# PWR_MGMT.net
KiCad netlist of a schematic drawn in Altium Designer
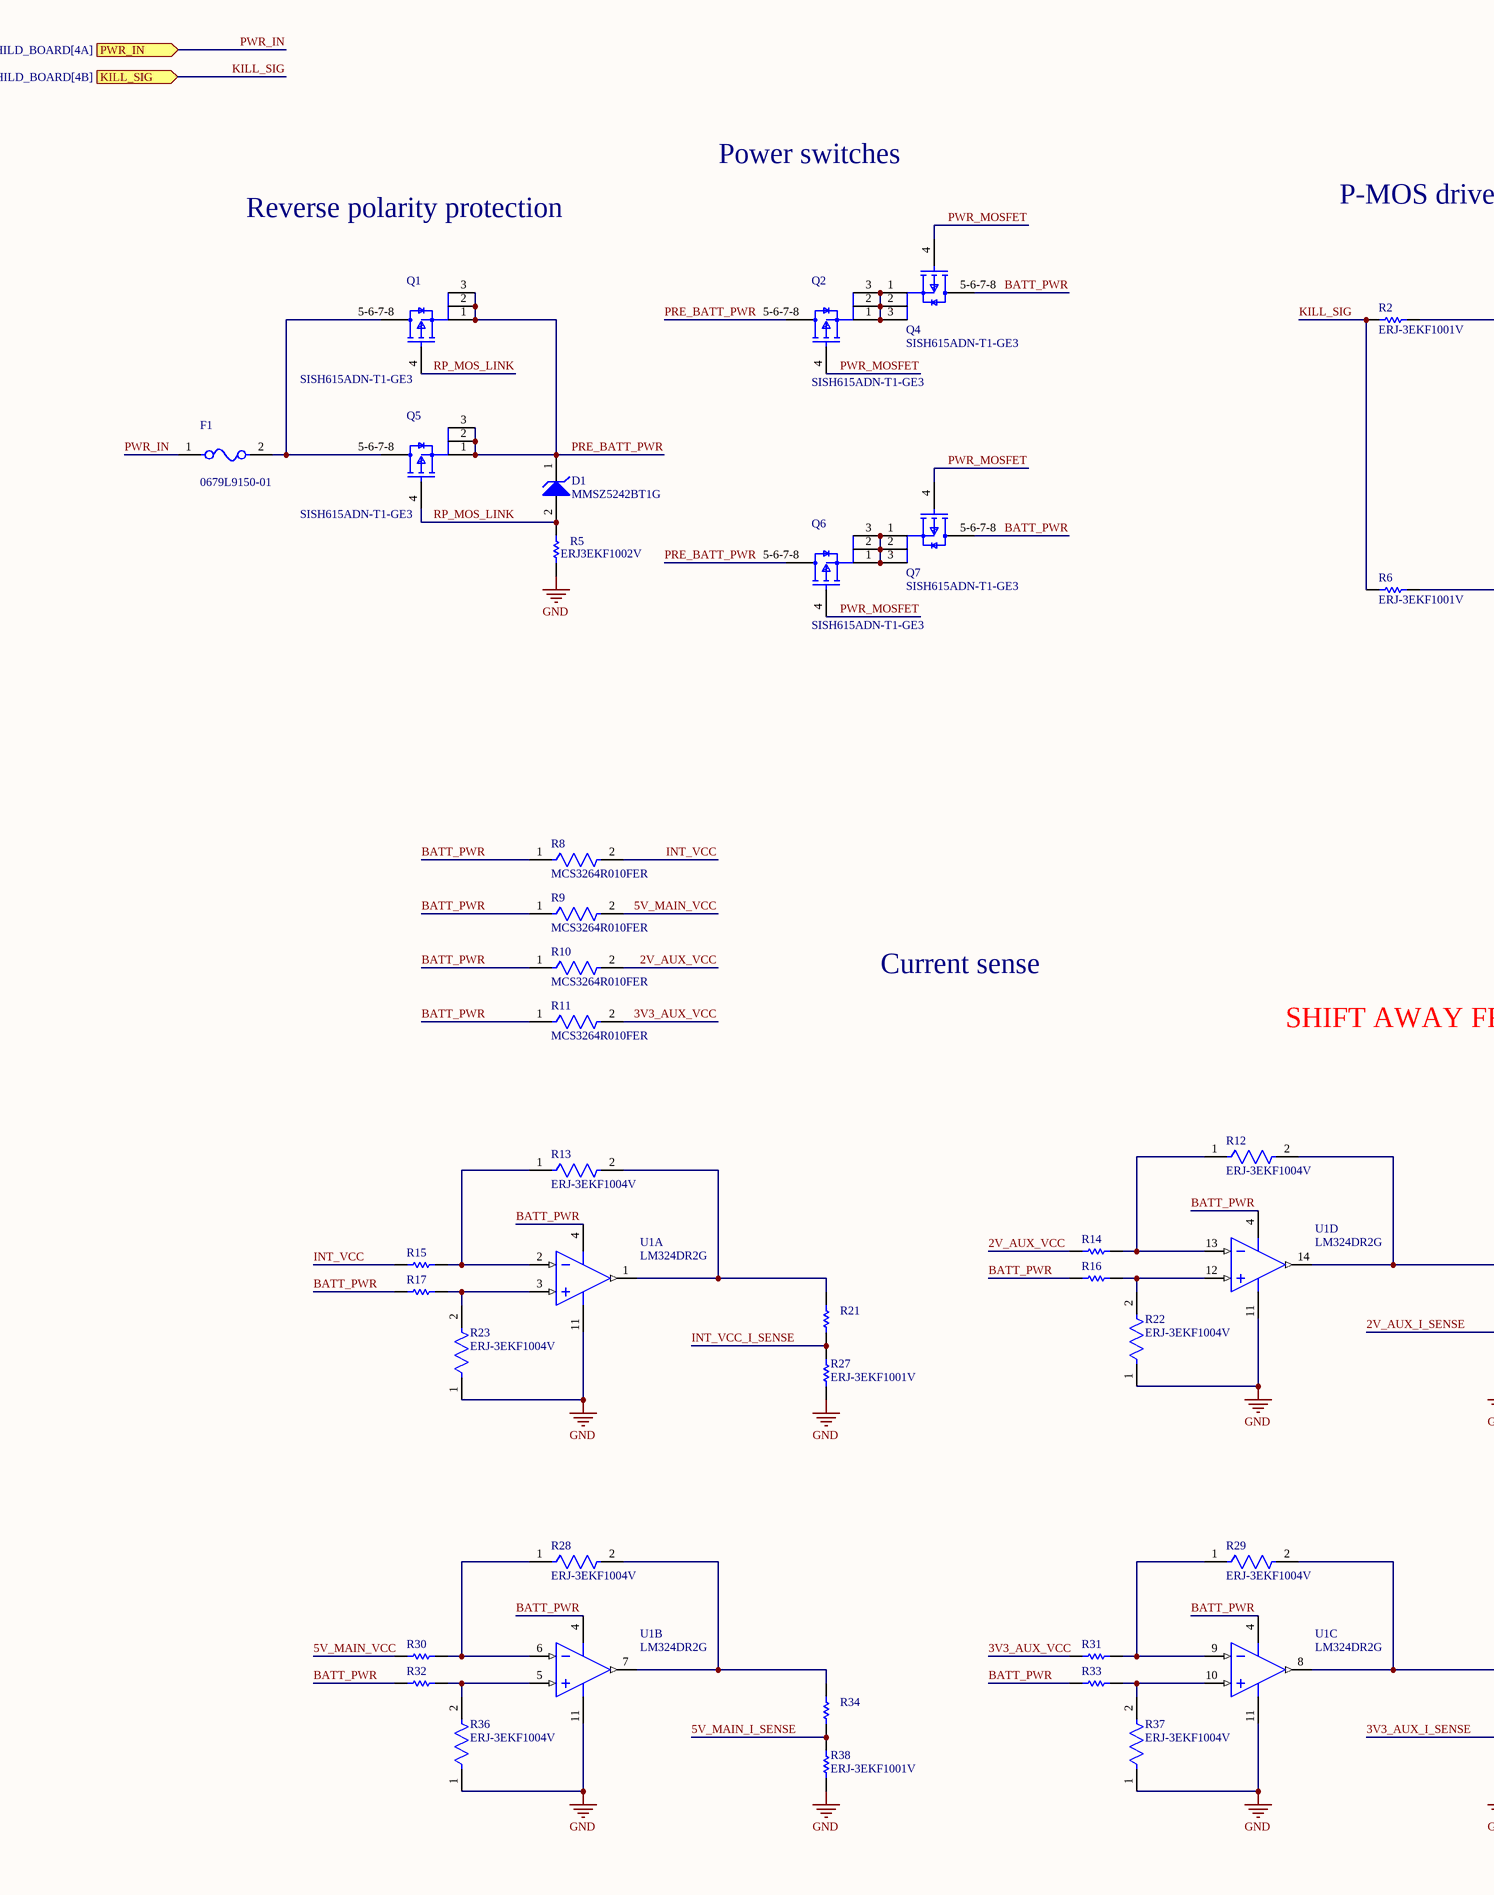
[diagram p0: PWR_MGMT.SchDoc, left]
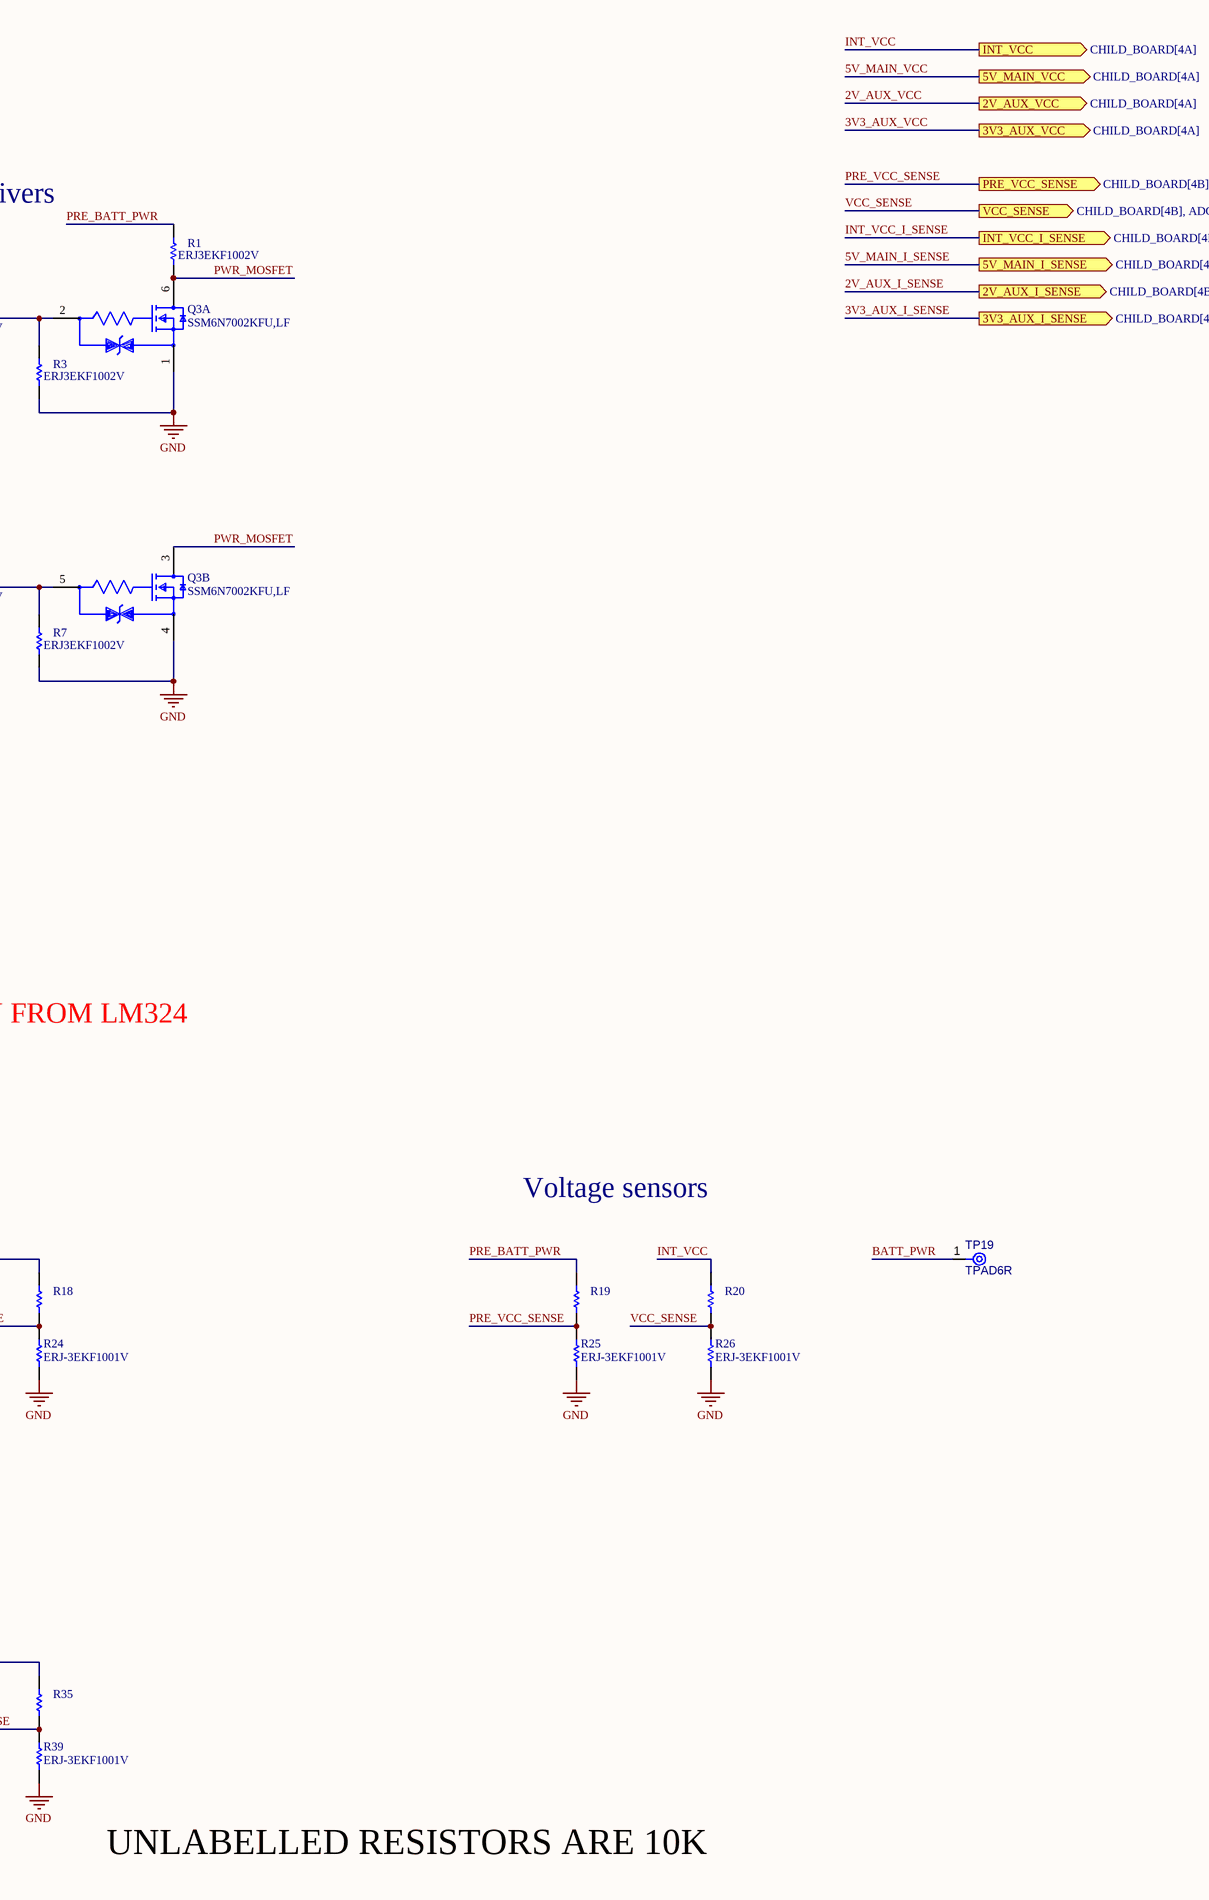
[diagram p1: PWR_MGMT.SchDoc, right]

(export (version "E")
  (design (tool "Eeschema 10.0.6"))
  (components
    (comp (ref "D1")
      (value "MMSZ5242BT1G")
      (footprint "ONSC-SOD-123-2-425-04_V")
      (description "Zener Voltage Regulator, 500 mW, 2-Pin SOD-123, Pb-Free, Tape and Reel")
      (fields (field (name "MANUFACTURER") "On Semiconductor"))
      (libsource (lib "Altium Content Vault") (part "ONSC-K1A2-2"))
    )
    (comp (ref "F1")
      (value "0679L9150-01")
      (footprint "FP-0679L-MFG")
      (description "FUSE BRD MNT 15A 125VAC/VDC")
      (fields
        (field (name "OCTOPART") "https://octopart.com/0679l9150-01-bel+fuse-70850665")
        (field (name "MANUFACTURER") "Bel Fuse")
      )
      (libsource (lib "Altium Content Vault") (part "5bcf9b9f640e542cf0359d10258e979"))
    )
    (comp (ref "Q1")
      (value "SISH615ADN-T1-GE3")
      (footprint "SISH615ADN-T1-GE3-Footprint-1")
      (description "Trans MOSFET P-CH 20V 22.1A 8-Pin PowerPAK 1212 EP T/R")
      (libsource (lib "uORocketry Hardware") (part "SISH615ADN-T1-GE3-Symbol-1"))
    )
    (comp (ref "Q2")
      (value "SISH615ADN-T1-GE3")
      (footprint "SISH615ADN-T1-GE3-Footprint-1")
      (description "Trans MOSFET P-CH 20V 22.1A 8-Pin PowerPAK 1212 EP T/R")
      (libsource (lib "uORocketry Hardware") (part "SISH615ADN-T1-GE3-Symbol-1"))
    )
    (comp (ref "Q3")
      (value "SSM6N7002KFU,LF")
      (footprint "FP-SSOP6-P-0_65A-MFG")
      (description "MOSFET 2N-CH 60V 0.3A")
      (libsource (lib "Altium Content Vault") (part "088aa6ac103fdeebe0d1c52ece6b7b9"))
    )
    (comp (ref "Q4")
      (value "SISH615ADN-T1-GE3")
      (footprint "SISH615ADN-T1-GE3-Footprint-1")
      (description "Trans MOSFET P-CH 20V 22.1A 8-Pin PowerPAK 1212 EP T/R")
      (libsource (lib "uORocketry Hardware") (part "SISH615ADN-T1-GE3-Symbol-1"))
    )
    (comp (ref "Q5")
      (value "SISH615ADN-T1-GE3")
      (footprint "SISH615ADN-T1-GE3-Footprint-1")
      (description "Trans MOSFET P-CH 20V 22.1A 8-Pin PowerPAK 1212 EP T/R")
      (libsource (lib "uORocketry Hardware") (part "SISH615ADN-T1-GE3-Symbol-1"))
    )
    (comp (ref "Q6")
      (value "SISH615ADN-T1-GE3")
      (footprint "SISH615ADN-T1-GE3-Footprint-1")
      (description "Trans MOSFET P-CH 20V 22.1A 8-Pin PowerPAK 1212 EP T/R")
      (libsource (lib "uORocketry Hardware") (part "SISH615ADN-T1-GE3-Symbol-1"))
    )
    (comp (ref "Q7")
      (value "SISH615ADN-T1-GE3")
      (footprint "SISH615ADN-T1-GE3-Footprint-1")
      (description "Trans MOSFET P-CH 20V 22.1A 8-Pin PowerPAK 1212 EP T/R")
      (libsource (lib "uORocketry Hardware") (part "SISH615ADN-T1-GE3-Symbol-1"))
    )
    (comp (ref "R1")
      (value "ERJ3EKF1002V")
      (footprint "RESC1609X55X30LL15T15")
      (description "Chip Resistor, 10 KOhm, +/- 1%, 0.1 W, -55 to 155 degC, 0603 (1608 Metric), RoHS, Tape and Reel")
      (fields (field (name "TOLERANCE") "1%") (field (name "MANUFACTURER") "Panasonic"))
      (libsource (lib "Altium Content Vault") (part "RES-2"))
    )
    (comp (ref "R2")
      (value "ERJ-3EKF1001V")
      (footprint "RESC1608X55X30LL15T15")
      (fields (field (name "MANUFACTURER") "Panasonic"))
      (libsource (lib "Altium Content Vault") (part "RES"))
    )
    (comp (ref "R3")
      (value "ERJ3EKF1002V")
      (footprint "RESC1609X55X30LL15T15")
      (description "Chip Resistor, 10 KOhm, +/- 1%, 0.1 W, -55 to 155 degC, 0603 (1608 Metric), RoHS, Tape and Reel")
      (fields (field (name "TOLERANCE") "1%") (field (name "MANUFACTURER") "Panasonic"))
      (libsource (lib "Altium Content Vault") (part "RES-2"))
    )
    (comp (ref "R5")
      (value "ERJ3EKF1002V")
      (footprint "RESC1609X55X30LL15T15")
      (description "Chip Resistor, 10 KOhm, +/- 1%, 0.1 W, -55 to 155 degC, 0603 (1608 Metric), RoHS, Tape and Reel")
      (fields (field (name "TOLERANCE") "1%") (field (name "MANUFACTURER") "Panasonic"))
      (libsource (lib "Altium Content Vault") (part "RES-2"))
    )
    (comp (ref "R6")
      (value "ERJ-3EKF1001V")
      (footprint "RESC1608X55X30LL15T15")
      (fields (field (name "MANUFACTURER") "Panasonic"))
      (libsource (lib "Altium Content Vault") (part "RES"))
    )
    (comp (ref "R7")
      (value "ERJ3EKF1002V")
      (footprint "RESC1609X55X30LL15T15")
      (description "Chip Resistor, 10 KOhm, +/- 1%, 0.1 W, -55 to 155 degC, 0603 (1608 Metric), RoHS, Tape and Reel")
      (fields (field (name "TOLERANCE") "1%") (field (name "MANUFACTURER") "Panasonic"))
      (libsource (lib "Altium Content Vault") (part "RES-2"))
    )
    (comp (ref "R8")
      (value "MCS3264R010FER")
      (footprint "FP-MCS3264-MFG")
      (description "RES SMD 10 MOHM 1% 2W 3264")
      (fields (field (name "TOLERANCE") "1%"))
      (libsource (lib "Altium Content Vault") (part "1029c3af85768c4190bb7ad29bc67b5"))
    )
    (comp (ref "R9")
      (value "MCS3264R010FER")
      (footprint "FP-MCS3264-MFG")
      (description "RES SMD 10 MOHM 1% 2W 3264")
      (fields (field (name "TOLERANCE") "1%"))
      (libsource (lib "Altium Content Vault") (part "1029c3af85768c4190bb7ad29bc67b5"))
    )
    (comp (ref "R10")
      (value "MCS3264R010FER")
      (footprint "FP-MCS3264-MFG")
      (description "RES SMD 10 MOHM 1% 2W 3264")
      (fields (field (name "TOLERANCE") "1%"))
      (libsource (lib "Altium Content Vault") (part "1029c3af85768c4190bb7ad29bc67b5"))
    )
    (comp (ref "R11")
      (value "MCS3264R010FER")
      (footprint "FP-MCS3264-MFG")
      (description "RES SMD 10 MOHM 1% 2W 3264")
      (fields (field (name "TOLERANCE") "1%"))
      (libsource (lib "Altium Content Vault") (part "1029c3af85768c4190bb7ad29bc67b5"))
    )
    (comp (ref "R12")
      (value "ERJ-3EKF1004V")
      (footprint "FP-ERJ3EK-IPC_C")
      (description "RES SMD 1M OHM 1% 1/10W 0603")
      (fields (field (name "TOLERANCE") "1%"))
      (libsource (lib "Altium Content Vault") (part "1029c3af85768c4190bb7ad29bc67b5"))
    )
    (comp (ref "R13")
      (value "ERJ-3EKF1004V")
      (footprint "FP-ERJ3EK-IPC_C")
      (description "RES SMD 1M OHM 1% 1/10W 0603")
      (fields (field (name "TOLERANCE") "1%"))
      (libsource (lib "Altium Content Vault") (part "1029c3af85768c4190bb7ad29bc67b5"))
    )
    (comp (ref "R14")
      (value "ERJ3EKF1002V")
      (footprint "RESC1609X55X30LL15T15")
      (description "Chip Resistor, 10 KOhm, +/- 1%, 0.1 W, -55 to 155 degC, 0603 (1608 Metric), RoHS, Tape and Reel")
      (fields (field (name "TOLERANCE") "1%") (field (name "MANUFACTURER") "Panasonic"))
      (libsource (lib "Altium Content Vault") (part "RES-2"))
    )
    (comp (ref "R15")
      (value "ERJ3EKF1002V")
      (footprint "RESC1609X55X30LL15T15")
      (description "Chip Resistor, 10 KOhm, +/- 1%, 0.1 W, -55 to 155 degC, 0603 (1608 Metric), RoHS, Tape and Reel")
      (fields (field (name "TOLERANCE") "1%") (field (name "MANUFACTURER") "Panasonic"))
      (libsource (lib "Altium Content Vault") (part "RES-2"))
    )
    (comp (ref "R16")
      (value "ERJ3EKF1002V")
      (footprint "RESC1609X55X30LL15T15")
      (description "Chip Resistor, 10 KOhm, +/- 1%, 0.1 W, -55 to 155 degC, 0603 (1608 Metric), RoHS, Tape and Reel")
      (fields (field (name "TOLERANCE") "1%") (field (name "MANUFACTURER") "Panasonic"))
      (libsource (lib "Altium Content Vault") (part "RES-2"))
    )
    (comp (ref "R17")
      (value "ERJ3EKF1002V")
      (footprint "RESC1609X55X30LL15T15")
      (description "Chip Resistor, 10 KOhm, +/- 1%, 0.1 W, -55 to 155 degC, 0603 (1608 Metric), RoHS, Tape and Reel")
      (fields (field (name "TOLERANCE") "1%") (field (name "MANUFACTURER") "Panasonic"))
      (libsource (lib "Altium Content Vault") (part "RES-2"))
    )
    (comp (ref "R18")
      (value "ERJ3EKF1002V")
      (footprint "RESC1609X55X30LL15T15")
      (description "Chip Resistor, 10 KOhm, +/- 1%, 0.1 W, -55 to 155 degC, 0603 (1608 Metric), RoHS, Tape and Reel")
      (fields (field (name "TOLERANCE") "1%") (field (name "MANUFACTURER") "Panasonic"))
      (libsource (lib "Altium Content Vault") (part "RES-2"))
    )
    (comp (ref "R19")
      (value "ERJ3EKF1002V")
      (footprint "RESC1609X55X30LL15T15")
      (description "Chip Resistor, 10 KOhm, +/- 1%, 0.1 W, -55 to 155 degC, 0603 (1608 Metric), RoHS, Tape and Reel")
      (fields (field (name "TOLERANCE") "1%") (field (name "MANUFACTURER") "Panasonic"))
      (libsource (lib "Altium Content Vault") (part "RES-2"))
    )
    (comp (ref "R20")
      (value "ERJ3EKF1002V")
      (footprint "RESC1609X55X30LL15T15")
      (description "Chip Resistor, 10 KOhm, +/- 1%, 0.1 W, -55 to 155 degC, 0603 (1608 Metric), RoHS, Tape and Reel")
      (fields (field (name "TOLERANCE") "1%") (field (name "MANUFACTURER") "Panasonic"))
      (libsource (lib "Altium Content Vault") (part "RES-2"))
    )
    (comp (ref "R21")
      (value "ERJ3EKF1002V")
      (footprint "RESC1609X55X30LL15T15")
      (description "Chip Resistor, 10 KOhm, +/- 1%, 0.1 W, -55 to 155 degC, 0603 (1608 Metric), RoHS, Tape and Reel")
      (fields (field (name "TOLERANCE") "1%") (field (name "MANUFACTURER") "Panasonic"))
      (libsource (lib "Altium Content Vault") (part "RES-2"))
    )
    (comp (ref "R22")
      (value "ERJ-3EKF1004V")
      (footprint "FP-ERJ3EK-IPC_C")
      (description "RES SMD 1M OHM 1% 1/10W 0603")
      (fields (field (name "TOLERANCE") "1%"))
      (libsource (lib "Altium Content Vault") (part "1029c3af85768c4190bb7ad29bc67b5"))
    )
    (comp (ref "R23")
      (value "ERJ-3EKF1004V")
      (footprint "FP-ERJ3EK-IPC_C")
      (description "RES SMD 1M OHM 1% 1/10W 0603")
      (fields (field (name "TOLERANCE") "1%"))
      (libsource (lib "Altium Content Vault") (part "1029c3af85768c4190bb7ad29bc67b5"))
    )
    (comp (ref "R24")
      (value "ERJ-3EKF1001V")
      (footprint "RESC1608X55X30LL15T15")
      (fields (field (name "MANUFACTURER") "Panasonic"))
      (libsource (lib "Altium Content Vault") (part "RES"))
    )
    (comp (ref "R25")
      (value "ERJ-3EKF1001V")
      (footprint "RESC1608X55X30LL15T15")
      (fields (field (name "MANUFACTURER") "Panasonic"))
      (libsource (lib "Altium Content Vault") (part "RES"))
    )
    (comp (ref "R26")
      (value "ERJ-3EKF1001V")
      (footprint "RESC1608X55X30LL15T15")
      (fields (field (name "MANUFACTURER") "Panasonic"))
      (libsource (lib "Altium Content Vault") (part "RES"))
    )
    (comp (ref "R27")
      (value "ERJ-3EKF1001V")
      (footprint "RESC1608X55X30LL15T15")
      (fields (field (name "MANUFACTURER") "Panasonic"))
      (libsource (lib "Altium Content Vault") (part "RES"))
    )
    (comp (ref "R28")
      (value "ERJ-3EKF1004V")
      (footprint "FP-ERJ3EK-IPC_C")
      (description "RES SMD 1M OHM 1% 1/10W 0603")
      (fields (field (name "TOLERANCE") "1%"))
      (libsource (lib "Altium Content Vault") (part "1029c3af85768c4190bb7ad29bc67b5"))
    )
    (comp (ref "R29")
      (value "ERJ-3EKF1004V")
      (footprint "FP-ERJ3EK-IPC_C")
      (description "RES SMD 1M OHM 1% 1/10W 0603")
      (fields (field (name "TOLERANCE") "1%"))
      (libsource (lib "Altium Content Vault") (part "1029c3af85768c4190bb7ad29bc67b5"))
    )
    (comp (ref "R30")
      (value "ERJ3EKF1002V")
      (footprint "RESC1609X55X30LL15T15")
      (description "Chip Resistor, 10 KOhm, +/- 1%, 0.1 W, -55 to 155 degC, 0603 (1608 Metric), RoHS, Tape and Reel")
      (fields (field (name "TOLERANCE") "1%") (field (name "MANUFACTURER") "Panasonic"))
      (libsource (lib "Altium Content Vault") (part "RES-2"))
    )
    (comp (ref "R31")
      (value "ERJ3EKF1002V")
      (footprint "RESC1609X55X30LL15T15")
      (description "Chip Resistor, 10 KOhm, +/- 1%, 0.1 W, -55 to 155 degC, 0603 (1608 Metric), RoHS, Tape and Reel")
      (fields (field (name "TOLERANCE") "1%") (field (name "MANUFACTURER") "Panasonic"))
      (libsource (lib "Altium Content Vault") (part "RES-2"))
    )
    (comp (ref "R32")
      (value "ERJ3EKF1002V")
      (footprint "RESC1609X55X30LL15T15")
      (description "Chip Resistor, 10 KOhm, +/- 1%, 0.1 W, -55 to 155 degC, 0603 (1608 Metric), RoHS, Tape and Reel")
      (fields (field (name "TOLERANCE") "1%") (field (name "MANUFACTURER") "Panasonic"))
      (libsource (lib "Altium Content Vault") (part "RES-2"))
    )
    (comp (ref "R33")
      (value "ERJ3EKF1002V")
      (footprint "RESC1609X55X30LL15T15")
      (description "Chip Resistor, 10 KOhm, +/- 1%, 0.1 W, -55 to 155 degC, 0603 (1608 Metric), RoHS, Tape and Reel")
      (fields (field (name "TOLERANCE") "1%") (field (name "MANUFACTURER") "Panasonic"))
      (libsource (lib "Altium Content Vault") (part "RES-2"))
    )
    (comp (ref "R34")
      (value "ERJ3EKF1002V")
      (footprint "RESC1609X55X30LL15T15")
      (description "Chip Resistor, 10 KOhm, +/- 1%, 0.1 W, -55 to 155 degC, 0603 (1608 Metric), RoHS, Tape and Reel")
      (fields (field (name "TOLERANCE") "1%") (field (name "MANUFACTURER") "Panasonic"))
      (libsource (lib "Altium Content Vault") (part "RES-2"))
    )
    (comp (ref "R35")
      (value "ERJ3EKF1002V")
      (footprint "RESC1609X55X30LL15T15")
      (description "Chip Resistor, 10 KOhm, +/- 1%, 0.1 W, -55 to 155 degC, 0603 (1608 Metric), RoHS, Tape and Reel")
      (fields (field (name "TOLERANCE") "1%") (field (name "MANUFACTURER") "Panasonic"))
      (libsource (lib "Altium Content Vault") (part "RES-2"))
    )
    (comp (ref "R36")
      (value "ERJ-3EKF1004V")
      (footprint "FP-ERJ3EK-IPC_C")
      (description "RES SMD 1M OHM 1% 1/10W 0603")
      (fields (field (name "TOLERANCE") "1%"))
      (libsource (lib "Altium Content Vault") (part "1029c3af85768c4190bb7ad29bc67b5"))
    )
    (comp (ref "R37")
      (value "ERJ-3EKF1004V")
      (footprint "FP-ERJ3EK-IPC_C")
      (description "RES SMD 1M OHM 1% 1/10W 0603")
      (fields (field (name "TOLERANCE") "1%"))
      (libsource (lib "Altium Content Vault") (part "1029c3af85768c4190bb7ad29bc67b5"))
    )
    (comp (ref "R38")
      (value "ERJ-3EKF1001V")
      (footprint "RESC1608X55X30LL15T15")
      (fields (field (name "MANUFACTURER") "Panasonic"))
      (libsource (lib "Altium Content Vault") (part "RES"))
    )
    (comp (ref "R39")
      (value "ERJ-3EKF1001V")
      (footprint "RESC1608X55X30LL15T15")
      (fields (field (name "MANUFACTURER") "Panasonic"))
      (libsource (lib "Altium Content Vault") (part "RES"))
    )
    (comp (ref "TP19")
      (value "TPAD6R")
      (footprint "TP06R")
      (description "0.6mm round")
      (libsource (lib "uORocketry Hardware") (part "CMP-001-0001-4"))
    )
    (comp (ref "U1")
      (value "LM324DR2G")
      (footprint "ONSC-SOIC-14-751A-03_V")
      (fields (field (name "MANUFACTURER") "On Semiconductor"))
      (libsource (lib "Altium Content Vault") (part "ONSC-LM224_324_2902_NCV2902-14"))
    )
  )
  (nets
    (net (code "1") (name "/2V_AUX_I_SENSE") (class "Default")
      (node (ref "R18") (pin "2") (pinfunction "2_2") (pintype "passive"))
      (node (ref "R24") (pin "2") (pinfunction "2_2") (pintype "passive"))
    )
    (net (code "2") (name "/2V_AUX_VCC") (class "Default")
      (node (ref "R10") (pin "2") (pinfunction "2_2") (pintype "passive"))
      (node (ref "R14") (pin "1") (pinfunction "1_1") (pintype "passive"))
    )
    (net (code "3") (name "/3V3_AUX_I_SENSE") (class "Default")
      (node (ref "R35") (pin "2") (pinfunction "2_2") (pintype "passive"))
      (node (ref "R39") (pin "2") (pinfunction "2_2") (pintype "passive"))
    )
    (net (code "4") (name "/3V3_AUX_VCC") (class "Default")
      (node (ref "R11") (pin "2") (pinfunction "2_2") (pintype "passive"))
      (node (ref "R31") (pin "1") (pinfunction "1_1") (pintype "passive"))
    )
    (net (code "5") (name "/5V_MAIN_I_SENSE") (class "Default")
      (node (ref "R34") (pin "2") (pinfunction "2_2") (pintype "passive"))
      (node (ref "R38") (pin "2") (pinfunction "2_2") (pintype "passive"))
    )
    (net (code "6") (name "/5V_MAIN_VCC") (class "Default")
      (node (ref "R30") (pin "1") (pinfunction "1_1") (pintype "passive"))
      (node (ref "R9") (pin "2") (pinfunction "2_2") (pintype "passive"))
    )
    (net (code "7") (name "/BATT_PWR") (class "Default")
      (node (ref "Q4") (pin "5-6-7-8") (pinfunction "D_5-6-7-8") (pintype "passive"))
      (node (ref "Q7") (pin "5-6-7-8") (pinfunction "D_5-6-7-8") (pintype "passive"))
      (node (ref "R10") (pin "1") (pinfunction "1_1") (pintype "passive"))
      (node (ref "R11") (pin "1") (pinfunction "1_1") (pintype "passive"))
      (node (ref "R16") (pin "1") (pinfunction "1_1") (pintype "passive"))
      (node (ref "R17") (pin "1") (pinfunction "1_1") (pintype "passive"))
      (node (ref "R32") (pin "1") (pinfunction "1_1") (pintype "passive"))
      (node (ref "R33") (pin "1") (pinfunction "1_1") (pintype "passive"))
      (node (ref "R8") (pin "1") (pinfunction "1_1") (pintype "passive"))
      (node (ref "R9") (pin "1") (pinfunction "1_1") (pintype "passive"))
      (node (ref "TP19") (pin "1") (pinfunction "TP_1") (pintype "passive"))
      (node (ref "U1") (pin "4") (pinfunction "VCC_4") (pintype "power_in"))
    )
    (net (code "8") (name "/INT_VCC") (class "Default")
      (node (ref "R15") (pin "1") (pinfunction "1_1") (pintype "passive"))
      (node (ref "R20") (pin "1") (pinfunction "1_1") (pintype "passive"))
      (node (ref "R8") (pin "2") (pinfunction "2_2") (pintype "passive"))
    )
    (net (code "9") (name "/INT_VCC_I_SENSE") (class "Default")
      (node (ref "R21") (pin "2") (pinfunction "2_2") (pintype "passive"))
      (node (ref "R27") (pin "2") (pinfunction "2_2") (pintype "passive"))
    )
    (net (code "10") (name "/KILL_SIG") (class "Default")
      (node (ref "R2") (pin "1") (pinfunction "1_1") (pintype "passive"))
      (node (ref "R6") (pin "1") (pinfunction "1_1") (pintype "passive"))
    )
    (net (code "11") (name "/PRE_BATT_PWR") (class "Default")
      (node (ref "D1") (pin "1") (pinfunction "K_1") (pintype "passive"))
      (node (ref "Q1") (pin "1") (pinfunction "S_1") (pintype "passive"))
      (node (ref "Q1") (pin "2") (pinfunction "S_2") (pintype "passive"))
      (node (ref "Q1") (pin "3") (pinfunction "S_3") (pintype "passive"))
      (node (ref "Q2") (pin "5-6-7-8") (pinfunction "D_5-6-7-8") (pintype "passive"))
      (node (ref "Q5") (pin "1") (pinfunction "S_1") (pintype "passive"))
      (node (ref "Q5") (pin "2") (pinfunction "S_2") (pintype "passive"))
      (node (ref "Q5") (pin "3") (pinfunction "S_3") (pintype "passive"))
      (node (ref "Q6") (pin "5-6-7-8") (pinfunction "D_5-6-7-8") (pintype "passive"))
      (node (ref "R1") (pin "1") (pinfunction "1_1") (pintype "passive"))
      (node (ref "R19") (pin "1") (pinfunction "1_1") (pintype "passive"))
    )
    (net (code "12") (name "/PRE_VCC_SENSE") (class "Default")
      (node (ref "R19") (pin "2") (pinfunction "2_2") (pintype "passive"))
      (node (ref "R25") (pin "2") (pinfunction "2_2") (pintype "passive"))
    )
    (net (code "13") (name "/PWR_IN") (class "Default")
      (node (ref "F1") (pin "1") (pinfunction "1_1") (pintype "passive"))
    )
    (net (code "14") (name "/PWR_MOSFET") (class "Default")
      (node (ref "Q2") (pin "4") (pinfunction "G_4") (pintype "passive"))
      (node (ref "Q3") (pin "3") (pinfunction "Drain2_3") (pintype "passive"))
      (node (ref "Q3") (pin "6") (pinfunction "Drain1_6") (pintype "passive"))
      (node (ref "Q4") (pin "4") (pinfunction "G_4") (pintype "passive"))
      (node (ref "Q6") (pin "4") (pinfunction "G_4") (pintype "passive"))
      (node (ref "Q7") (pin "4") (pinfunction "G_4") (pintype "passive"))
      (node (ref "R1") (pin "2") (pinfunction "2_2") (pintype "passive"))
    )
    (net (code "15") (name "/RP_MOS_LINK") (class "Default")
      (node (ref "D1") (pin "2") (pinfunction "A_2") (pintype "passive"))
      (node (ref "Q1") (pin "4") (pinfunction "G_4") (pintype "passive"))
      (node (ref "Q5") (pin "4") (pinfunction "G_4") (pintype "passive"))
      (node (ref "R5") (pin "1") (pinfunction "1_1") (pintype "passive"))
    )
    (net (code "16") (name "/VCC_SENSE") (class "Default")
      (node (ref "R20") (pin "2") (pinfunction "2_2") (pintype "passive"))
      (node (ref "R26") (pin "2") (pinfunction "2_2") (pintype "passive"))
    )
    (net (code "17") (name "GND") (class "Default")
      (node (ref "Q3") (pin "1") (pinfunction "Source1_1") (pintype "passive"))
      (node (ref "Q3") (pin "4") (pinfunction "Source2_4") (pintype "passive"))
      (node (ref "R22") (pin "1") (pinfunction "1_1") (pintype "passive"))
      (node (ref "R23") (pin "1") (pinfunction "1_1") (pintype "passive"))
      (node (ref "R24") (pin "1") (pinfunction "1_1") (pintype "passive"))
      (node (ref "R25") (pin "1") (pinfunction "1_1") (pintype "passive"))
      (node (ref "R26") (pin "1") (pinfunction "1_1") (pintype "passive"))
      (node (ref "R27") (pin "1") (pinfunction "1_1") (pintype "passive"))
      (node (ref "R3") (pin "2") (pinfunction "2_2") (pintype "passive"))
      (node (ref "R36") (pin "1") (pinfunction "1_1") (pintype "passive"))
      (node (ref "R37") (pin "1") (pinfunction "1_1") (pintype "passive"))
      (node (ref "R38") (pin "1") (pinfunction "1_1") (pintype "passive"))
      (node (ref "R39") (pin "1") (pinfunction "1_1") (pintype "passive"))
      (node (ref "R5") (pin "2") (pinfunction "2_2") (pintype "passive"))
      (node (ref "R7") (pin "2") (pinfunction "2_2") (pintype "passive"))
      (node (ref "U1") (pin "11") (pinfunction "VEE/GND_11") (pintype "power_in"))
    )
    (net (code "18") (name "Net-(Q1-D)") (class "Default")
      (node (ref "F1") (pin "2") (pinfunction "2_2") (pintype "passive"))
      (node (ref "Q1") (pin "5-6-7-8") (pinfunction "D_5-6-7-8") (pintype "passive"))
      (node (ref "Q5") (pin "5-6-7-8") (pinfunction "D_5-6-7-8") (pintype "passive"))
    )
    (net (code "19") (name "Net-(Q2-S-Pad1)") (class "Default")
      (node (ref "Q2") (pin "1") (pinfunction "S_1") (pintype "passive"))
      (node (ref "Q2") (pin "2") (pinfunction "S_2") (pintype "passive"))
      (node (ref "Q2") (pin "3") (pinfunction "S_3") (pintype "passive"))
      (node (ref "Q4") (pin "1") (pinfunction "S_1") (pintype "passive"))
      (node (ref "Q4") (pin "2") (pinfunction "S_2") (pintype "passive"))
      (node (ref "Q4") (pin "3") (pinfunction "S_3") (pintype "passive"))
    )
    (net (code "20") (name "Net-(Q3A-Gate1)") (class "Default")
      (node (ref "Q3") (pin "2") (pinfunction "Gate1_2") (pintype "passive"))
      (node (ref "R2") (pin "2") (pinfunction "2_2") (pintype "passive"))
      (node (ref "R3") (pin "1") (pinfunction "1_1") (pintype "passive"))
    )
    (net (code "21") (name "Net-(Q3B-Gate2)") (class "Default")
      (node (ref "Q3") (pin "5") (pinfunction "Gate2_5") (pintype "passive"))
      (node (ref "R6") (pin "2") (pinfunction "2_2") (pintype "passive"))
      (node (ref "R7") (pin "1") (pinfunction "1_1") (pintype "passive"))
    )
    (net (code "22") (name "Net-(Q6-S-Pad1)") (class "Default")
      (node (ref "Q6") (pin "1") (pinfunction "S_1") (pintype "passive"))
      (node (ref "Q6") (pin "2") (pinfunction "S_2") (pintype "passive"))
      (node (ref "Q6") (pin "3") (pinfunction "S_3") (pintype "passive"))
      (node (ref "Q7") (pin "1") (pinfunction "S_1") (pintype "passive"))
      (node (ref "Q7") (pin "2") (pinfunction "S_2") (pintype "passive"))
      (node (ref "Q7") (pin "3") (pinfunction "S_3") (pintype "passive"))
    )
    (net (code "23") (name "Net-(U1A-IN1+)") (class "Default")
      (node (ref "R17") (pin "2") (pinfunction "2_2") (pintype "passive"))
      (node (ref "R23") (pin "2") (pinfunction "2_2") (pintype "passive"))
      (node (ref "U1") (pin "3") (pinfunction "IN1+_3") (pintype "input"))
    )
    (net (code "24") (name "Net-(U1A-IN1-)") (class "Default")
      (node (ref "R13") (pin "1") (pinfunction "1_1") (pintype "passive"))
      (node (ref "R15") (pin "2") (pinfunction "2_2") (pintype "passive"))
      (node (ref "U1") (pin "2") (pinfunction "IN1-_2") (pintype "input"))
    )
    (net (code "25") (name "Net-(U1A-OUT1)") (class "Default")
      (node (ref "R13") (pin "2") (pinfunction "2_2") (pintype "passive"))
      (node (ref "R21") (pin "1") (pinfunction "1_1") (pintype "passive"))
      (node (ref "U1") (pin "1") (pinfunction "OUT1_1") (pintype "output"))
    )
    (net (code "26") (name "Net-(U1B-IN2+)") (class "Default")
      (node (ref "R32") (pin "2") (pinfunction "2_2") (pintype "passive"))
      (node (ref "R36") (pin "2") (pinfunction "2_2") (pintype "passive"))
      (node (ref "U1") (pin "5") (pinfunction "IN2+_5") (pintype "input"))
    )
    (net (code "27") (name "Net-(U1B-IN2-)") (class "Default")
      (node (ref "R28") (pin "1") (pinfunction "1_1") (pintype "passive"))
      (node (ref "R30") (pin "2") (pinfunction "2_2") (pintype "passive"))
      (node (ref "U1") (pin "6") (pinfunction "IN2-_6") (pintype "input"))
    )
    (net (code "28") (name "Net-(U1B-OUT2)") (class "Default")
      (node (ref "R28") (pin "2") (pinfunction "2_2") (pintype "passive"))
      (node (ref "R34") (pin "1") (pinfunction "1_1") (pintype "passive"))
      (node (ref "U1") (pin "7") (pinfunction "OUT2_7") (pintype "output"))
    )
    (net (code "29") (name "Net-(U1C-IN3+)") (class "Default")
      (node (ref "R33") (pin "2") (pinfunction "2_2") (pintype "passive"))
      (node (ref "R37") (pin "2") (pinfunction "2_2") (pintype "passive"))
      (node (ref "U1") (pin "10") (pinfunction "IN3+_10") (pintype "input"))
    )
    (net (code "30") (name "Net-(U1C-IN3-)") (class "Default")
      (node (ref "R29") (pin "1") (pinfunction "1_1") (pintype "passive"))
      (node (ref "R31") (pin "2") (pinfunction "2_2") (pintype "passive"))
      (node (ref "U1") (pin "9") (pinfunction "IN3-_9") (pintype "input"))
    )
    (net (code "31") (name "Net-(U1C-OUT3)") (class "Default")
      (node (ref "R29") (pin "2") (pinfunction "2_2") (pintype "passive"))
      (node (ref "R35") (pin "1") (pinfunction "1_1") (pintype "passive"))
      (node (ref "U1") (pin "8") (pinfunction "OUT3_8") (pintype "output"))
    )
    (net (code "32") (name "Net-(U1D-IN4+)") (class "Default")
      (node (ref "R16") (pin "2") (pinfunction "2_2") (pintype "passive"))
      (node (ref "R22") (pin "2") (pinfunction "2_2") (pintype "passive"))
      (node (ref "U1") (pin "12") (pinfunction "IN4+_12") (pintype "input"))
    )
    (net (code "33") (name "Net-(U1D-IN4-)") (class "Default")
      (node (ref "R12") (pin "1") (pinfunction "1_1") (pintype "passive"))
      (node (ref "R14") (pin "2") (pinfunction "2_2") (pintype "passive"))
      (node (ref "U1") (pin "13") (pinfunction "IN4-_13") (pintype "input"))
    )
    (net (code "34") (name "Net-(U1D-OUT4)") (class "Default")
      (node (ref "R12") (pin "2") (pinfunction "2_2") (pintype "passive"))
      (node (ref "R18") (pin "1") (pinfunction "1_1") (pintype "passive"))
      (node (ref "U1") (pin "14") (pinfunction "OUT4_14") (pintype "output"))
    )
  )
)
